# feather-load-tester.net
KiCad netlist of a schematic drawn in EAGLE
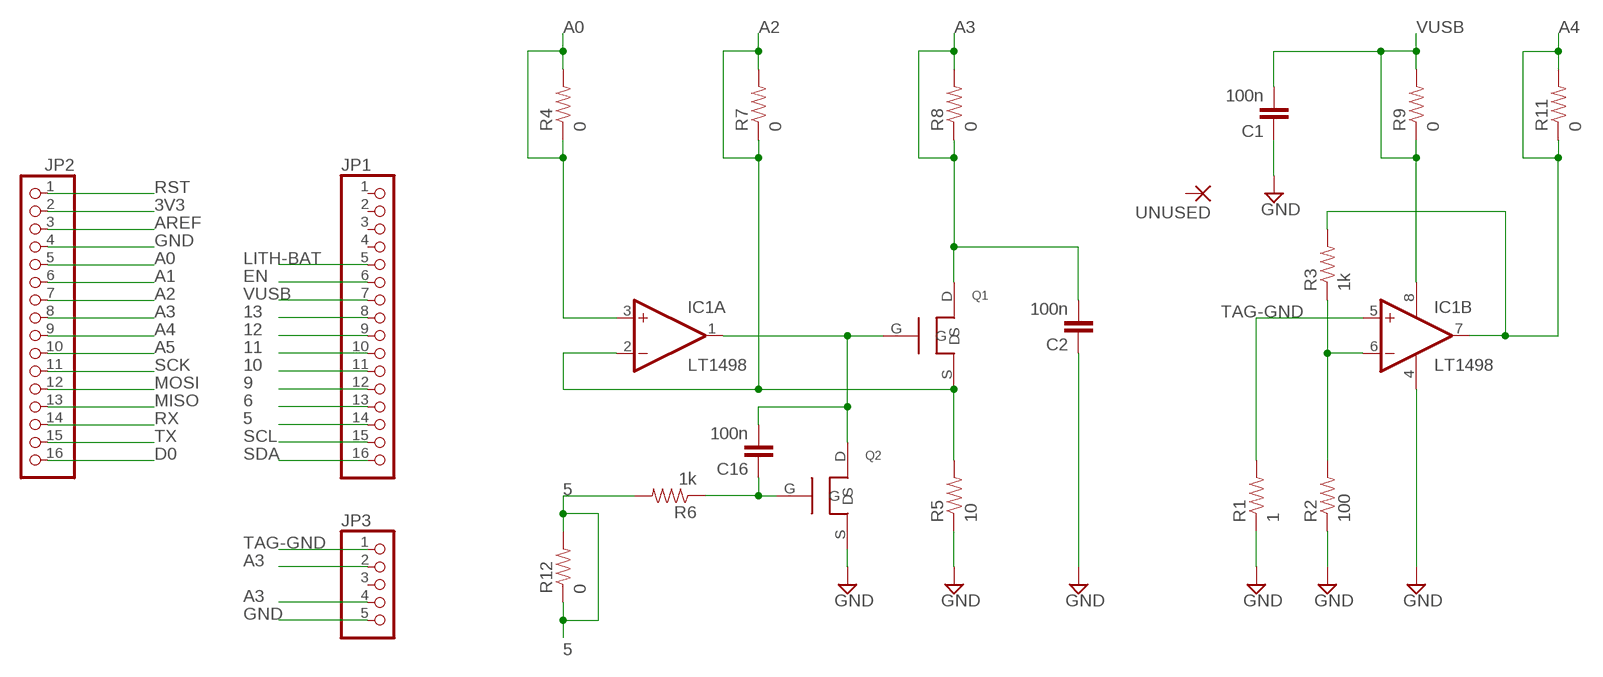
[diagram p0: schematic, sheet 1]

(export (version "E")
  (design (tool "Eeschema 10.0.6"))
  (components
    (comp (ref "C1")
      (value "100n")
      (footprint "eagle-import:0805-CAP")
      (libsource (lib "eagle-import") (part "0.33UF-50V-10%(0805)"))
    )
    (comp (ref "C2")
      (value "100n")
      (footprint "eagle-import:0805-CAP")
      (libsource (lib "eagle-import") (part "0.33UF-50V-10%(0805)"))
    )
    (comp (ref "C16")
      (value "100n")
      (footprint "eagle-import:0805-CAP")
      (libsource (lib "eagle-import") (part "0.33UF-50V-10%(0805)"))
    )
    (comp (ref "IC1")
      (value "LT1498")
      (footprint "eagle-import:SO08")
      (libsource (lib "eagle-import") (part "2AMP_P8+4D"))
    )
    (comp (ref "JP1")
      (value "PINHD-1X16")
      (footprint "eagle-import:1X16")
      (libsource (lib "eagle-import") (part "PINHD-1X16"))
    )
    (comp (ref "JP2")
      (value "PINHD-1X16")
      (footprint "eagle-import:1X16")
      (libsource (lib "eagle-import") (part "PINHD-1X16"))
    )
    (comp (ref "JP3")
      (value "PINHD-1X5")
      (footprint "eagle-import:1X05")
      (libsource (lib "eagle-import") (part "PINHD-1X5"))
    )
    (comp (ref "Q1")
      (value "NMOSFET_SC59")
      (footprint "eagle-import:SC59")
      (fields (field (name "MANUFACTURER") "Diodes Inc.") (field (name "MPN") "DMN1019UFDE-7"))
      (libsource (lib "eagle-import") (part "NMOSFET_SC59"))
    )
    (comp (ref "Q2")
      (value "NMOSFET_SC59")
      (footprint "eagle-import:SC59")
      (fields (field (name "MANUFACTURER") "Diodes Inc.") (field (name "MPN") "DMN1019UFDE-7"))
      (libsource (lib "eagle-import") (part "NMOSFET_SC59"))
    )
    (comp (ref "R1")
      (value "1")
      (footprint "eagle-import:0805")
      (libsource (lib "eagle-import") (part "0.22OHM-1/4W-1%(0805)"))
    )
    (comp (ref "R2")
      (value "100")
      (footprint "eagle-import:0805")
      (libsource (lib "eagle-import") (part "0.22OHM-1/4W-1%(0805)"))
    )
    (comp (ref "R3")
      (value "1k")
      (footprint "eagle-import:0805")
      (libsource (lib "eagle-import") (part "0.22OHM-1/4W-1%(0805)"))
    )
    (comp (ref "R4")
      (value "0")
      (footprint "eagle-import:0805")
      (libsource (lib "eagle-import") (part "0.22OHM-1/4W-1%(0805)"))
    )
    (comp (ref "R5")
      (value "10")
      (footprint "eagle-import:0805")
      (libsource (lib "eagle-import") (part "0.22OHM-1/4W-1%(0805)"))
    )
    (comp (ref "R6")
      (value "1k")
      (footprint "eagle-import:0805")
      (libsource (lib "eagle-import") (part "0.22OHM-1/4W-1%(0805)"))
    )
    (comp (ref "R7")
      (value "0")
      (footprint "eagle-import:0805")
      (libsource (lib "eagle-import") (part "0.22OHM-1/4W-1%(0805)"))
    )
    (comp (ref "R8")
      (value "0")
      (footprint "eagle-import:0805")
      (libsource (lib "eagle-import") (part "0.22OHM-1/4W-1%(0805)"))
    )
    (comp (ref "R9")
      (value "0")
      (footprint "eagle-import:0805")
      (libsource (lib "eagle-import") (part "0.22OHM-1/4W-1%(0805)"))
    )
    (comp (ref "R11")
      (value "0")
      (footprint "eagle-import:0805")
      (libsource (lib "eagle-import") (part "0.22OHM-1/4W-1%(0805)"))
    )
    (comp (ref "R12")
      (value "0")
      (footprint "eagle-import:0805")
      (libsource (lib "eagle-import") (part "0.22OHM-1/4W-1%(0805)"))
    )
    (comp (ref "UNUSED")
      (value "SMD2")
      (footprint "eagle-import:SMD1,27-2,54")
      (libsource (lib "eagle-import") (part "SMD2"))
    )
  )
  (nets
    (net (code "1") (name "/3V3") (class "Default")
      (node (ref "JP2") (pin "2") (pinfunction "2_2") (pintype "passive"))
    )
    (net (code "2") (name "/5") (class "Default")
      (node (ref "JP1") (pin "14") (pinfunction "14_14") (pintype "passive"))
      (node (ref "R12") (pin "1") (pinfunction "1_1") (pintype "passive"))
      (node (ref "R12") (pin "2") (pinfunction "2_2") (pintype "passive"))
      (node (ref "R6") (pin "2") (pinfunction "2_2") (pintype "passive"))
    )
    (net (code "3") (name "/6") (class "Default")
      (node (ref "JP1") (pin "13") (pinfunction "13_13") (pintype "passive"))
    )
    (net (code "4") (name "/9") (class "Default")
      (node (ref "JP1") (pin "12") (pinfunction "12_12") (pintype "passive"))
    )
    (net (code "5") (name "/10") (class "Default")
      (node (ref "JP1") (pin "11") (pinfunction "11_11") (pintype "passive"))
    )
    (net (code "6") (name "/11") (class "Default")
      (node (ref "JP1") (pin "10") (pinfunction "10_10") (pintype "passive"))
    )
    (net (code "7") (name "/12") (class "Default")
      (node (ref "JP1") (pin "9") (pinfunction "9_9") (pintype "passive"))
    )
    (net (code "8") (name "/13") (class "Default")
      (node (ref "JP1") (pin "8") (pinfunction "8_8") (pintype "passive"))
    )
    (net (code "9") (name "/A0") (class "Default")
      (node (ref "IC1") (pin "3") (pinfunction "+IN_3") (pintype "input"))
      (node (ref "JP2") (pin "5") (pinfunction "5_5") (pintype "passive"))
      (node (ref "R4") (pin "1") (pinfunction "1_1") (pintype "passive"))
      (node (ref "R4") (pin "2") (pinfunction "2_2") (pintype "passive"))
    )
    (net (code "10") (name "/A1") (class "Default")
      (node (ref "JP2") (pin "6") (pinfunction "6_6") (pintype "passive"))
    )
    (net (code "11") (name "/A2") (class "Default")
      (node (ref "IC1") (pin "2") (pinfunction "-IN_2") (pintype "input"))
      (node (ref "JP2") (pin "7") (pinfunction "7_7") (pintype "passive"))
      (node (ref "Q1") (pin "S") (pinfunction "S_S") (pintype "bidirectional"))
      (node (ref "R5") (pin "2") (pinfunction "2_2") (pintype "passive"))
      (node (ref "R7") (pin "1") (pinfunction "1_1") (pintype "passive"))
      (node (ref "R7") (pin "2") (pinfunction "2_2") (pintype "passive"))
    )
    (net (code "12") (name "/A3") (class "Default")
      (node (ref "C2") (pin "2") (pinfunction "2_2") (pintype "passive"))
      (node (ref "JP2") (pin "8") (pinfunction "8_8") (pintype "passive"))
      (node (ref "JP3") (pin "2") (pinfunction "2_2") (pintype "passive"))
      (node (ref "JP3") (pin "4") (pinfunction "4_4") (pintype "passive"))
      (node (ref "Q1") (pin "D") (pinfunction "D_D") (pintype "bidirectional"))
      (node (ref "R8") (pin "1") (pinfunction "1_1") (pintype "passive"))
      (node (ref "R8") (pin "2") (pinfunction "2_2") (pintype "passive"))
    )
    (net (code "13") (name "/A4") (class "Default")
      (node (ref "IC1") (pin "7") (pinfunction "OUT_7") (pintype "output"))
      (node (ref "JP2") (pin "9") (pinfunction "9_9") (pintype "passive"))
      (node (ref "R11") (pin "1") (pinfunction "1_1") (pintype "passive"))
      (node (ref "R11") (pin "2") (pinfunction "2_2") (pintype "passive"))
      (node (ref "R3") (pin "2") (pinfunction "2_2") (pintype "passive"))
    )
    (net (code "14") (name "/A5") (class "Default")
      (node (ref "JP2") (pin "10") (pinfunction "10_10") (pintype "passive"))
    )
    (net (code "15") (name "/AREF") (class "Default")
      (node (ref "JP2") (pin "3") (pinfunction "3_3") (pintype "passive"))
    )
    (net (code "16") (name "/D0") (class "Default")
      (node (ref "JP2") (pin "16") (pinfunction "16_16") (pintype "passive"))
    )
    (net (code "17") (name "/EN") (class "Default")
      (node (ref "JP1") (pin "6") (pinfunction "6_6") (pintype "passive"))
    )
    (net (code "18") (name "/LITH-BAT") (class "Default")
      (node (ref "JP1") (pin "5") (pinfunction "5_5") (pintype "passive"))
    )
    (net (code "19") (name "/MISO") (class "Default")
      (node (ref "JP2") (pin "13") (pinfunction "13_13") (pintype "passive"))
    )
    (net (code "20") (name "/MOSI") (class "Default")
      (node (ref "JP2") (pin "12") (pinfunction "12_12") (pintype "passive"))
    )
    (net (code "21") (name "/RST") (class "Default")
      (node (ref "JP2") (pin "1") (pinfunction "1_1") (pintype "passive"))
    )
    (net (code "22") (name "/RX") (class "Default")
      (node (ref "JP2") (pin "14") (pinfunction "14_14") (pintype "passive"))
    )
    (net (code "23") (name "/SCK") (class "Default")
      (node (ref "JP2") (pin "11") (pinfunction "11_11") (pintype "passive"))
    )
    (net (code "24") (name "/SCL") (class "Default")
      (node (ref "JP1") (pin "15") (pinfunction "15_15") (pintype "passive"))
    )
    (net (code "25") (name "/SDA") (class "Default")
      (node (ref "JP1") (pin "16") (pinfunction "16_16") (pintype "passive"))
    )
    (net (code "26") (name "/TAG-GND") (class "Default")
      (node (ref "IC1") (pin "5") (pinfunction "+IN_5") (pintype "input"))
      (node (ref "JP3") (pin "1") (pinfunction "1_1") (pintype "passive"))
      (node (ref "R1") (pin "2") (pinfunction "2_2") (pintype "passive"))
    )
    (net (code "27") (name "/TX") (class "Default")
      (node (ref "JP2") (pin "15") (pinfunction "15_15") (pintype "passive"))
    )
    (net (code "28") (name "/VUSB") (class "Default")
      (node (ref "C1") (pin "2") (pinfunction "2_2") (pintype "passive"))
      (node (ref "IC1") (pin "8") (pinfunction "V+_8") (pintype "power_in"))
      (node (ref "JP1") (pin "7") (pinfunction "7_7") (pintype "passive"))
      (node (ref "R9") (pin "1") (pinfunction "1_1") (pintype "passive"))
      (node (ref "R9") (pin "2") (pinfunction "2_2") (pintype "passive"))
    )
    (net (code "29") (name "GND") (class "Default")
      (node (ref "C1") (pin "1") (pinfunction "1_1") (pintype "passive"))
      (node (ref "C2") (pin "1") (pinfunction "1_1") (pintype "passive"))
      (node (ref "IC1") (pin "4") (pinfunction "V-_4") (pintype "power_in"))
      (node (ref "JP2") (pin "4") (pinfunction "4_4") (pintype "passive"))
      (node (ref "JP3") (pin "5") (pinfunction "5_5") (pintype "passive"))
      (node (ref "Q2") (pin "S") (pinfunction "S_S") (pintype "bidirectional"))
      (node (ref "R1") (pin "1") (pinfunction "1_1") (pintype "passive"))
      (node (ref "R2") (pin "1") (pinfunction "1_1") (pintype "passive"))
      (node (ref "R5") (pin "1") (pinfunction "1_1") (pintype "passive"))
    )
    (net (code "30") (name "Net-(C16-Pad1)") (class "Default")
      (node (ref "C16") (pin "1") (pinfunction "1_1") (pintype "passive"))
      (node (ref "Q2") (pin "G") (pinfunction "G_G") (pintype "bidirectional"))
      (node (ref "R6") (pin "1") (pinfunction "1_1") (pintype "passive"))
    )
    (net (code "31") (name "Net-(IC1A-OUT)") (class "Default")
      (node (ref "C16") (pin "2") (pinfunction "2_2") (pintype "passive"))
      (node (ref "IC1") (pin "1") (pinfunction "OUT_1") (pintype "output"))
      (node (ref "Q1") (pin "G") (pinfunction "G_G") (pintype "bidirectional"))
      (node (ref "Q2") (pin "D") (pinfunction "D_D") (pintype "bidirectional"))
    )
    (net (code "32") (name "Net-(IC1B--IN)") (class "Default")
      (node (ref "IC1") (pin "6") (pinfunction "-IN_6") (pintype "input"))
      (node (ref "R2") (pin "2") (pinfunction "2_2") (pintype "passive"))
      (node (ref "R3") (pin "1") (pinfunction "1_1") (pintype "passive"))
    )
    (net (code "33") (name "unconnected-(JP1-Pad1)") (class "Default")
      (node (ref "JP1") (pin "1") (pinfunction "1_1") (pintype "passive"))
    )
    (net (code "34") (name "unconnected-(JP1-Pad2)") (class "Default")
      (node (ref "JP1") (pin "2") (pinfunction "2_2") (pintype "passive"))
    )
    (net (code "35") (name "unconnected-(JP1-Pad3)") (class "Default")
      (node (ref "JP1") (pin "3") (pinfunction "3_3") (pintype "passive"))
    )
    (net (code "36") (name "unconnected-(JP1-Pad4)") (class "Default")
      (node (ref "JP1") (pin "4") (pinfunction "4_4") (pintype "passive"))
    )
    (net (code "37") (name "unconnected-(JP3-Pad3)") (class "Default")
      (node (ref "JP3") (pin "3") (pinfunction "3_3") (pintype "passive"))
    )
    (net (code "38") (name "unconnected-(UNUSED-P-Pad1)") (class "Default")
      (node (ref "UNUSED") (pin "1") (pinfunction "P_1") (pintype "passive"))
    )
  )
)
